# led_control.net
KiCad netlist of a schematic drawn in Altium Designer
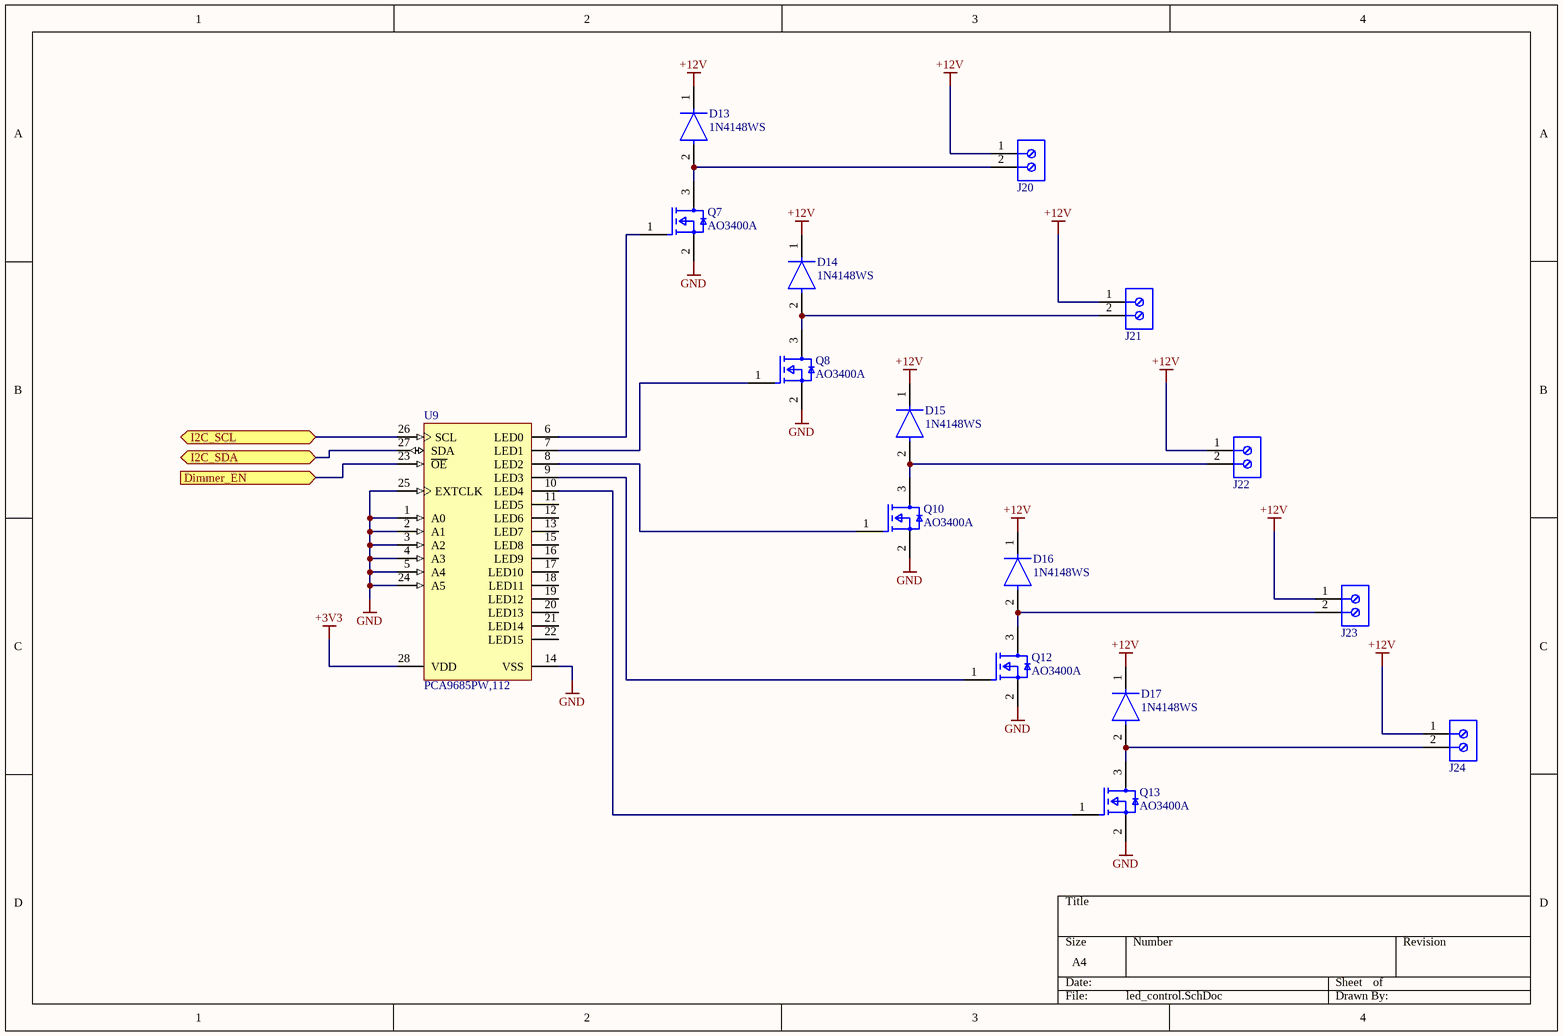
[diagram p0: led_control.SchDoc]

(export (version "E")
  (design (tool "Eeschema 10.0.6"))
  (components
    (comp (ref "D13")
      (value "1N4148WS")
      (footprint "FP-477AB-IPC_C")
      (description "DIODE GEN PURP 75V 150MA SOD323F")
      (libsource (lib "Altium Content Vault") (part "d7152d700b627762746794eb795d46e"))
    )
    (comp (ref "D14")
      (value "1N4148WS")
      (footprint "FP-477AB-IPC_C")
      (description "DIODE GEN PURP 75V 150MA SOD323F")
      (libsource (lib "Altium Content Vault") (part "d7152d700b627762746794eb795d46e"))
    )
    (comp (ref "D15")
      (value "1N4148WS")
      (footprint "FP-477AB-IPC_C")
      (description "DIODE GEN PURP 75V 150MA SOD323F")
      (libsource (lib "Altium Content Vault") (part "d7152d700b627762746794eb795d46e"))
    )
    (comp (ref "D16")
      (value "1N4148WS")
      (footprint "FP-477AB-IPC_C")
      (description "DIODE GEN PURP 75V 150MA SOD323F")
      (libsource (lib "Altium Content Vault") (part "d7152d700b627762746794eb795d46e"))
    )
    (comp (ref "D17")
      (value "1N4148WS")
      (footprint "FP-477AB-IPC_C")
      (description "DIODE GEN PURP 75V 150MA SOD323F")
      (libsource (lib "Altium Content Vault") (part "d7152d700b627762746794eb795d46e"))
    )
    (comp (ref "J20")
      (value "282836-2")
      (footprint "TECO-282836-2_V")
      (description "Female Header, Pitch 5 mm, 1 x 2 Position, Height 10 mm, Tail Length 3.5 mm, Rohs, Bulk")
      (fields (field (name "VOLTAGE") "300V") (field (name "MANUFACTURER") "TE Connectivity"))
      (libsource (lib "Altium Content Vault") (part "CN-1P-F-TB2"))
    )
    (comp (ref "J21")
      (value "282836-2")
      (footprint "TECO-282836-2_V")
      (description "Female Header, Pitch 5 mm, 1 x 2 Position, Height 10 mm, Tail Length 3.5 mm, Rohs, Bulk")
      (fields (field (name "VOLTAGE") "300V") (field (name "MANUFACTURER") "TE Connectivity"))
      (libsource (lib "Altium Content Vault") (part "CN-1P-F-TB2"))
    )
    (comp (ref "J22")
      (value "282836-2")
      (footprint "TECO-282836-2_V")
      (description "Female Header, Pitch 5 mm, 1 x 2 Position, Height 10 mm, Tail Length 3.5 mm, Rohs, Bulk")
      (fields (field (name "VOLTAGE") "300V") (field (name "MANUFACTURER") "TE Connectivity"))
      (libsource (lib "Altium Content Vault") (part "CN-1P-F-TB2"))
    )
    (comp (ref "J23")
      (value "282836-2")
      (footprint "TECO-282836-2_V")
      (description "Female Header, Pitch 5 mm, 1 x 2 Position, Height 10 mm, Tail Length 3.5 mm, Rohs, Bulk")
      (fields (field (name "VOLTAGE") "300V") (field (name "MANUFACTURER") "TE Connectivity"))
      (libsource (lib "Altium Content Vault") (part "CN-1P-F-TB2"))
    )
    (comp (ref "J24")
      (value "282836-2")
      (footprint "TECO-282836-2_V")
      (description "Female Header, Pitch 5 mm, 1 x 2 Position, Height 10 mm, Tail Length 3.5 mm, Rohs, Bulk")
      (fields (field (name "VOLTAGE") "300V") (field (name "MANUFACTURER") "TE Connectivity"))
      (libsource (lib "Altium Content Vault") (part "CN-1P-F-TB2"))
    )
    (comp (ref "Q7")
      (value "AO3400A")
      (footprint "SOT-23")
      (description "MOSFET N-CH 30V 5.7A SOT23")
      (libsource (lib "integrated_library") (part "MOSFET_AO3400A"))
    )
    (comp (ref "Q8")
      (value "AO3400A")
      (footprint "SOT-23")
      (description "MOSFET N-CH 30V 5.7A SOT23")
      (libsource (lib "integrated_library") (part "MOSFET_AO3400A"))
    )
    (comp (ref "Q10")
      (value "AO3400A")
      (footprint "SOT-23")
      (description "MOSFET N-CH 30V 5.7A SOT23")
      (libsource (lib "integrated_library") (part "MOSFET_AO3400A"))
    )
    (comp (ref "Q12")
      (value "AO3400A")
      (footprint "SOT-23")
      (description "MOSFET N-CH 30V 5.7A SOT23")
      (libsource (lib "integrated_library") (part "MOSFET_AO3400A"))
    )
    (comp (ref "Q13")
      (value "AO3400A")
      (footprint "SOT-23")
      (description "MOSFET N-CH 30V 5.7A SOT23")
      (libsource (lib "integrated_library") (part "MOSFET_AO3400A"))
    )
    (comp (ref "U9")
      (value "PCA9685PW,112")
      (footprint "SOT361-1_V")
      (fields (field (name "PARTNUMBER") "PCA9685"))
      (libsource (lib "Altium Content Vault") (part "NXP-PCA9685-SOT361-1"))
    )
  )
  (nets
    (net (code "1") (name "+3V3") (class "Default")
      (node (ref "U9") (pin "28") (pinfunction "VDD_28") (pintype "power_in"))
    )
    (net (code "2") (name "+12V") (class "Default")
      (node (ref "D13") (pin "1") (pinfunction "C_1") (pintype "passive"))
      (node (ref "D14") (pin "1") (pinfunction "C_1") (pintype "passive"))
      (node (ref "D15") (pin "1") (pinfunction "C_1") (pintype "passive"))
      (node (ref "D16") (pin "1") (pinfunction "C_1") (pintype "passive"))
      (node (ref "D17") (pin "1") (pinfunction "C_1") (pintype "passive"))
      (node (ref "J20") (pin "1") (pinfunction "1_1") (pintype "passive"))
      (node (ref "J21") (pin "1") (pinfunction "1_1") (pintype "passive"))
      (node (ref "J22") (pin "1") (pinfunction "1_1") (pintype "passive"))
      (node (ref "J23") (pin "1") (pinfunction "1_1") (pintype "passive"))
      (node (ref "J24") (pin "1") (pinfunction "1_1") (pintype "passive"))
    )
    (net (code "3") (name "/Dimmer_EN") (class "Default")
      (node (ref "U9") (pin "23") (pinfunction "~{OE}_23") (pintype "input"))
    )
    (net (code "4") (name "/I2C_SCL") (class "Default")
      (node (ref "U9") (pin "26") (pinfunction "SCL_26") (pintype "input"))
    )
    (net (code "5") (name "/I2C_SDA") (class "Default")
      (node (ref "U9") (pin "27") (pinfunction "SDA_27") (pintype "bidirectional"))
    )
    (net (code "6") (name "GND") (class "Default")
      (node (ref "Q10") (pin "2") (pinfunction "S_2") (pintype "passive"))
      (node (ref "Q12") (pin "2") (pinfunction "S_2") (pintype "passive"))
      (node (ref "Q13") (pin "2") (pinfunction "S_2") (pintype "passive"))
      (node (ref "Q7") (pin "2") (pinfunction "S_2") (pintype "passive"))
      (node (ref "Q8") (pin "2") (pinfunction "S_2") (pintype "passive"))
      (node (ref "U9") (pin "1") (pinfunction "A0_1") (pintype "input"))
      (node (ref "U9") (pin "14") (pinfunction "VSS_14") (pintype "power_in"))
      (node (ref "U9") (pin "2") (pinfunction "A1_2") (pintype "input"))
      (node (ref "U9") (pin "24") (pinfunction "A5_24") (pintype "input"))
      (node (ref "U9") (pin "25") (pinfunction "EXTCLK_25") (pintype "input"))
      (node (ref "U9") (pin "3") (pinfunction "A2_3") (pintype "input"))
      (node (ref "U9") (pin "4") (pinfunction "A3_4") (pintype "input"))
      (node (ref "U9") (pin "5") (pinfunction "A4_5") (pintype "input"))
    )
    (net (code "7") (name "Net-(D13-A)") (class "Default")
      (node (ref "D13") (pin "2") (pinfunction "A_2") (pintype "passive"))
      (node (ref "J20") (pin "2") (pinfunction "2_2") (pintype "passive"))
      (node (ref "Q7") (pin "3") (pinfunction "D_3") (pintype "passive"))
    )
    (net (code "8") (name "Net-(D14-A)") (class "Default")
      (node (ref "D14") (pin "2") (pinfunction "A_2") (pintype "passive"))
      (node (ref "J21") (pin "2") (pinfunction "2_2") (pintype "passive"))
      (node (ref "Q8") (pin "3") (pinfunction "D_3") (pintype "passive"))
    )
    (net (code "9") (name "Net-(D15-A)") (class "Default")
      (node (ref "D15") (pin "2") (pinfunction "A_2") (pintype "passive"))
      (node (ref "J22") (pin "2") (pinfunction "2_2") (pintype "passive"))
      (node (ref "Q10") (pin "3") (pinfunction "D_3") (pintype "passive"))
    )
    (net (code "10") (name "Net-(D16-A)") (class "Default")
      (node (ref "D16") (pin "2") (pinfunction "A_2") (pintype "passive"))
      (node (ref "J23") (pin "2") (pinfunction "2_2") (pintype "passive"))
      (node (ref "Q12") (pin "3") (pinfunction "D_3") (pintype "passive"))
    )
    (net (code "11") (name "Net-(D17-A)") (class "Default")
      (node (ref "D17") (pin "2") (pinfunction "A_2") (pintype "passive"))
      (node (ref "J24") (pin "2") (pinfunction "2_2") (pintype "passive"))
      (node (ref "Q13") (pin "3") (pinfunction "D_3") (pintype "passive"))
    )
    (net (code "12") (name "Net-(Q7-G)") (class "Default")
      (node (ref "Q7") (pin "1") (pinfunction "G_1") (pintype "passive"))
      (node (ref "U9") (pin "6") (pinfunction "LED0_6") (pintype "tri_state"))
    )
    (net (code "13") (name "Net-(Q8-G)") (class "Default")
      (node (ref "Q8") (pin "1") (pinfunction "G_1") (pintype "passive"))
      (node (ref "U9") (pin "7") (pinfunction "LED1_7") (pintype "tri_state"))
    )
    (net (code "14") (name "Net-(Q10-G)") (class "Default")
      (node (ref "Q10") (pin "1") (pinfunction "G_1") (pintype "passive"))
      (node (ref "U9") (pin "8") (pinfunction "LED2_8") (pintype "tri_state"))
    )
    (net (code "15") (name "Net-(Q12-G)") (class "Default")
      (node (ref "Q12") (pin "1") (pinfunction "G_1") (pintype "passive"))
      (node (ref "U9") (pin "9") (pinfunction "LED3_9") (pintype "tri_state"))
    )
    (net (code "16") (name "Net-(Q13-G)") (class "Default")
      (node (ref "Q13") (pin "1") (pinfunction "G_1") (pintype "passive"))
      (node (ref "U9") (pin "10") (pinfunction "LED4_10") (pintype "tri_state"))
    )
    (net (code "17") (name "unconnected-(U9-LED5-Pad11)") (class "Default")
      (node (ref "U9") (pin "11") (pinfunction "LED5_11") (pintype "tri_state"))
    )
    (net (code "18") (name "unconnected-(U9-LED6-Pad12)") (class "Default")
      (node (ref "U9") (pin "12") (pinfunction "LED6_12") (pintype "tri_state"))
    )
    (net (code "19") (name "unconnected-(U9-LED7-Pad13)") (class "Default")
      (node (ref "U9") (pin "13") (pinfunction "LED7_13") (pintype "tri_state"))
    )
    (net (code "20") (name "unconnected-(U9-LED8-Pad15)") (class "Default")
      (node (ref "U9") (pin "15") (pinfunction "LED8_15") (pintype "tri_state"))
    )
    (net (code "21") (name "unconnected-(U9-LED9-Pad16)") (class "Default")
      (node (ref "U9") (pin "16") (pinfunction "LED9_16") (pintype "tri_state"))
    )
    (net (code "22") (name "unconnected-(U9-LED10-Pad17)") (class "Default")
      (node (ref "U9") (pin "17") (pinfunction "LED10_17") (pintype "tri_state"))
    )
    (net (code "23") (name "unconnected-(U9-LED11-Pad18)") (class "Default")
      (node (ref "U9") (pin "18") (pinfunction "LED11_18") (pintype "tri_state"))
    )
    (net (code "24") (name "unconnected-(U9-LED12-Pad19)") (class "Default")
      (node (ref "U9") (pin "19") (pinfunction "LED12_19") (pintype "tri_state"))
    )
    (net (code "25") (name "unconnected-(U9-LED13-Pad20)") (class "Default")
      (node (ref "U9") (pin "20") (pinfunction "LED13_20") (pintype "tri_state"))
    )
    (net (code "26") (name "unconnected-(U9-LED14-Pad21)") (class "Default")
      (node (ref "U9") (pin "21") (pinfunction "LED14_21") (pintype "tri_state"))
    )
    (net (code "27") (name "unconnected-(U9-LED15-Pad22)") (class "Default")
      (node (ref "U9") (pin "22") (pinfunction "LED15_22") (pintype "tri_state"))
    )
  )
)
